# klawiatura_Sony_ST120_v1.net
KiCad netlist of a schematic drawn in EAGLE
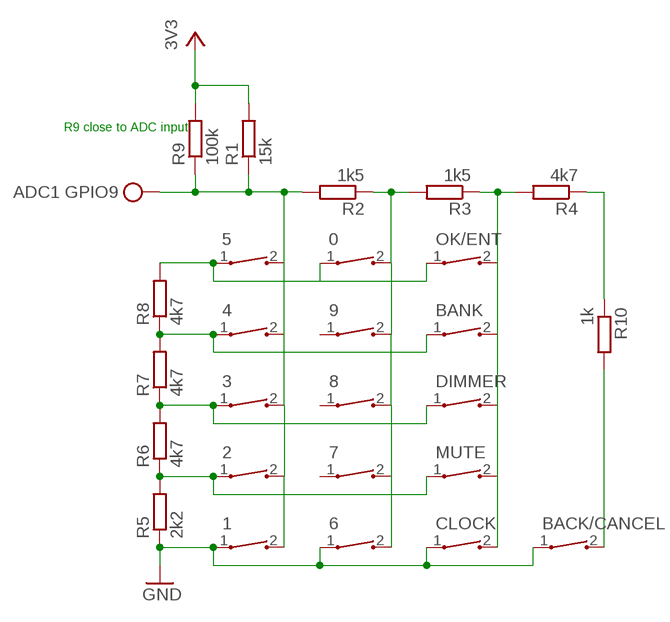
[diagram p0: schematic, sheet 1]

(export (version "E")
  (design (tool "Eeschema 10.0.6"))
  (components
    (comp (ref "0")
      (value "CT10-XXXX-A2")
      (footprint "eagle-import:CT10-XXXX-A2")
      (libsource (lib "eagle-import") (part "CT10-XXXX-A2"))
    )
    (comp (ref "1")
      (value "CT10-XXXX-A2")
      (footprint "eagle-import:CT10-XXXX-A2")
      (libsource (lib "eagle-import") (part "CT10-XXXX-A2"))
    )
    (comp (ref "2")
      (value "CT10-XXXX-A2")
      (footprint "eagle-import:CT10-XXXX-A2")
      (libsource (lib "eagle-import") (part "CT10-XXXX-A2"))
    )
    (comp (ref "3")
      (value "CT10-XXXX-A2")
      (footprint "eagle-import:CT10-XXXX-A2")
      (libsource (lib "eagle-import") (part "CT10-XXXX-A2"))
    )
    (comp (ref "4")
      (value "CT10-XXXX-A2")
      (footprint "eagle-import:CT10-XXXX-A2")
      (libsource (lib "eagle-import") (part "CT10-XXXX-A2"))
    )
    (comp (ref "5")
      (value "CT10-XXXX-A2")
      (footprint "eagle-import:CT10-XXXX-A2")
      (libsource (lib "eagle-import") (part "CT10-XXXX-A2"))
    )
    (comp (ref "6")
      (value "CT10-XXXX-A2")
      (footprint "eagle-import:CT10-XXXX-A2")
      (libsource (lib "eagle-import") (part "CT10-XXXX-A2"))
    )
    (comp (ref "7")
      (value "CT10-XXXX-A2")
      (footprint "eagle-import:CT10-XXXX-A2")
      (libsource (lib "eagle-import") (part "CT10-XXXX-A2"))
    )
    (comp (ref "8")
      (value "CT10-XXXX-A2")
      (footprint "eagle-import:CT10-XXXX-A2")
      (libsource (lib "eagle-import") (part "CT10-XXXX-A2"))
    )
    (comp (ref "9")
      (value "CT10-XXXX-A2")
      (footprint "eagle-import:CT10-XXXX-A2")
      (libsource (lib "eagle-import") (part "CT10-XXXX-A2"))
    )
    (comp (ref "BACK/CANCEL")
      (value "CT10-XXXX-A2")
      (footprint "eagle-import:CT10-XXXX-A2")
      (libsource (lib "eagle-import") (part "CT10-XXXX-A2"))
    )
    (comp (ref "BANK")
      (value "CT10-XXXX-A2")
      (footprint "eagle-import:CT10-XXXX-A2")
      (libsource (lib "eagle-import") (part "CT10-XXXX-A2"))
    )
    (comp (ref "CLOCK")
      (value "CT10-XXXX-A2")
      (footprint "eagle-import:CT10-XXXX-A2")
      (libsource (lib "eagle-import") (part "CT10-XXXX-A2"))
    )
    (comp (ref "DIMMER")
      (value "CT10-XXXX-A2")
      (footprint "eagle-import:CT10-XXXX-A2")
      (libsource (lib "eagle-import") (part "CT10-XXXX-A2"))
    )
    (comp (ref "MUTE")
      (value "CT10-XXXX-A2")
      (footprint "eagle-import:CT10-XXXX-A2")
      (libsource (lib "eagle-import") (part "CT10-XXXX-A2"))
    )
    (comp (ref "OK/ENT")
      (value "CT10-XXXX-A2")
      (footprint "eagle-import:CT10-XXXX-A2")
      (libsource (lib "eagle-import") (part "CT10-XXXX-A2"))
    )
    (comp (ref "R1")
      (value "15k")
      (footprint "eagle-import:0204_5")
      (libsource (lib "eagle-import") (part "R-EU_0204/5"))
    )
    (comp (ref "R2")
      (value "1k5")
      (footprint "eagle-import:0204_5")
      (libsource (lib "eagle-import") (part "R-EU_0204/5"))
    )
    (comp (ref "R3")
      (value "1k5")
      (footprint "eagle-import:0204_5")
      (libsource (lib "eagle-import") (part "R-EU_0204/5"))
    )
    (comp (ref "R4")
      (value "4k7")
      (footprint "eagle-import:0204_5")
      (libsource (lib "eagle-import") (part "R-EU_0204/5"))
    )
    (comp (ref "R5")
      (value "2k2")
      (footprint "eagle-import:0204_5")
      (libsource (lib "eagle-import") (part "R-EU_0204/5"))
    )
    (comp (ref "R6")
      (value "4k7")
      (footprint "eagle-import:0204_5")
      (libsource (lib "eagle-import") (part "R-EU_0204/5"))
    )
    (comp (ref "R7")
      (value "4k7")
      (footprint "eagle-import:0204_5")
      (libsource (lib "eagle-import") (part "R-EU_0204/5"))
    )
    (comp (ref "R8")
      (value "4k7")
      (footprint "eagle-import:0204_5")
      (libsource (lib "eagle-import") (part "R-EU_0204/5"))
    )
    (comp (ref "R9")
      (value "100k")
      (footprint "eagle-import:0204_5")
      (libsource (lib "eagle-import") (part "R-EU_0204/5"))
    )
    (comp (ref "R10")
      (value "1k")
      (footprint "eagle-import:0204_5")
      (libsource (lib "eagle-import") (part "R-EU_0204/5"))
    )
  )
  (nets
    (net (code "1") (name "3V3") (class "Default")
      (node (ref "1") (pin "2") (pinfunction "2_2") (pintype "passive"))
      (node (ref "2") (pin "2") (pinfunction "2_2") (pintype "passive"))
      (node (ref "3") (pin "2") (pinfunction "2_2") (pintype "passive"))
      (node (ref "4") (pin "2") (pinfunction "2_2") (pintype "passive"))
      (node (ref "5") (pin "2") (pinfunction "2_2") (pintype "passive"))
      (node (ref "R1") (pin "1") (pinfunction "1_1") (pintype "passive"))
      (node (ref "R1") (pin "2") (pinfunction "2_2") (pintype "passive"))
      (node (ref "R2") (pin "2") (pinfunction "2_2") (pintype "passive"))
      (node (ref "R9") (pin "1") (pinfunction "1_1") (pintype "passive"))
      (node (ref "R9") (pin "2") (pinfunction "2_2") (pintype "passive"))
    )
    (net (code "2") (name "GND") (class "Default")
      (node (ref "1") (pin "1") (pinfunction "1_1") (pintype "passive"))
      (node (ref "6") (pin "1") (pinfunction "1_1") (pintype "passive"))
      (node (ref "BACK/CANCEL") (pin "1") (pinfunction "1_1") (pintype "passive"))
      (node (ref "CLOCK") (pin "1") (pinfunction "1_1") (pintype "passive"))
      (node (ref "R5") (pin "1") (pinfunction "1_1") (pintype "passive"))
    )
    (net (code "3") (name "Net-(0-Pad1)") (class "Default")
      (node (ref "0") (pin "1") (pinfunction "1_1") (pintype "passive"))
      (node (ref "5") (pin "1") (pinfunction "1_1") (pintype "passive"))
      (node (ref "OK/ENT") (pin "1") (pinfunction "1_1") (pintype "passive"))
      (node (ref "R8") (pin "2") (pinfunction "2_2") (pintype "passive"))
    )
    (net (code "4") (name "Net-(0-Pad2)") (class "Default")
      (node (ref "0") (pin "2") (pinfunction "2_2") (pintype "passive"))
      (node (ref "6") (pin "2") (pinfunction "2_2") (pintype "passive"))
      (node (ref "7") (pin "2") (pinfunction "2_2") (pintype "passive"))
      (node (ref "8") (pin "2") (pinfunction "2_2") (pintype "passive"))
      (node (ref "9") (pin "2") (pinfunction "2_2") (pintype "passive"))
      (node (ref "R2") (pin "1") (pinfunction "1_1") (pintype "passive"))
      (node (ref "R3") (pin "2") (pinfunction "2_2") (pintype "passive"))
    )
    (net (code "5") (name "Net-(2-Pad1)") (class "Default")
      (node (ref "2") (pin "1") (pinfunction "1_1") (pintype "passive"))
      (node (ref "MUTE") (pin "1") (pinfunction "1_1") (pintype "passive"))
      (node (ref "R5") (pin "2") (pinfunction "2_2") (pintype "passive"))
      (node (ref "R6") (pin "1") (pinfunction "1_1") (pintype "passive"))
    )
    (net (code "6") (name "Net-(3-Pad1)") (class "Default")
      (node (ref "3") (pin "1") (pinfunction "1_1") (pintype "passive"))
      (node (ref "DIMMER") (pin "1") (pinfunction "1_1") (pintype "passive"))
      (node (ref "R6") (pin "2") (pinfunction "2_2") (pintype "passive"))
      (node (ref "R7") (pin "1") (pinfunction "1_1") (pintype "passive"))
    )
    (net (code "7") (name "Net-(4-Pad1)") (class "Default")
      (node (ref "4") (pin "1") (pinfunction "1_1") (pintype "passive"))
      (node (ref "BANK") (pin "1") (pinfunction "1_1") (pintype "passive"))
      (node (ref "R7") (pin "2") (pinfunction "2_2") (pintype "passive"))
      (node (ref "R8") (pin "1") (pinfunction "1_1") (pintype "passive"))
    )
    (net (code "8") (name "Net-(BACK/CANCEL-Pad2)") (class "Default")
      (node (ref "BACK/CANCEL") (pin "2") (pinfunction "2_2") (pintype "passive"))
      (node (ref "R10") (pin "2") (pinfunction "2_2") (pintype "passive"))
    )
    (net (code "9") (name "Net-(BANK-Pad2)") (class "Default")
      (node (ref "BANK") (pin "2") (pinfunction "2_2") (pintype "passive"))
      (node (ref "CLOCK") (pin "2") (pinfunction "2_2") (pintype "passive"))
      (node (ref "DIMMER") (pin "2") (pinfunction "2_2") (pintype "passive"))
      (node (ref "MUTE") (pin "2") (pinfunction "2_2") (pintype "passive"))
      (node (ref "OK/ENT") (pin "2") (pinfunction "2_2") (pintype "passive"))
      (node (ref "R3") (pin "1") (pinfunction "1_1") (pintype "passive"))
      (node (ref "R4") (pin "2") (pinfunction "2_2") (pintype "passive"))
    )
    (net (code "10") (name "Net-(R10-Pad1)") (class "Default")
      (node (ref "R10") (pin "1") (pinfunction "1_1") (pintype "passive"))
      (node (ref "R4") (pin "1") (pinfunction "1_1") (pintype "passive"))
    )
    (net (code "11") (name "unconnected-(7-Pad1)") (class "Default")
      (node (ref "7") (pin "1") (pinfunction "1_1") (pintype "passive"))
    )
    (net (code "12") (name "unconnected-(8-Pad1)") (class "Default")
      (node (ref "8") (pin "1") (pinfunction "1_1") (pintype "passive"))
    )
    (net (code "13") (name "unconnected-(9-Pad1)") (class "Default")
      (node (ref "9") (pin "1") (pinfunction "1_1") (pintype "passive"))
    )
  )
)
